# 6_Fans_Control.net
KiCad netlist of a schematic drawn in Altium Designer
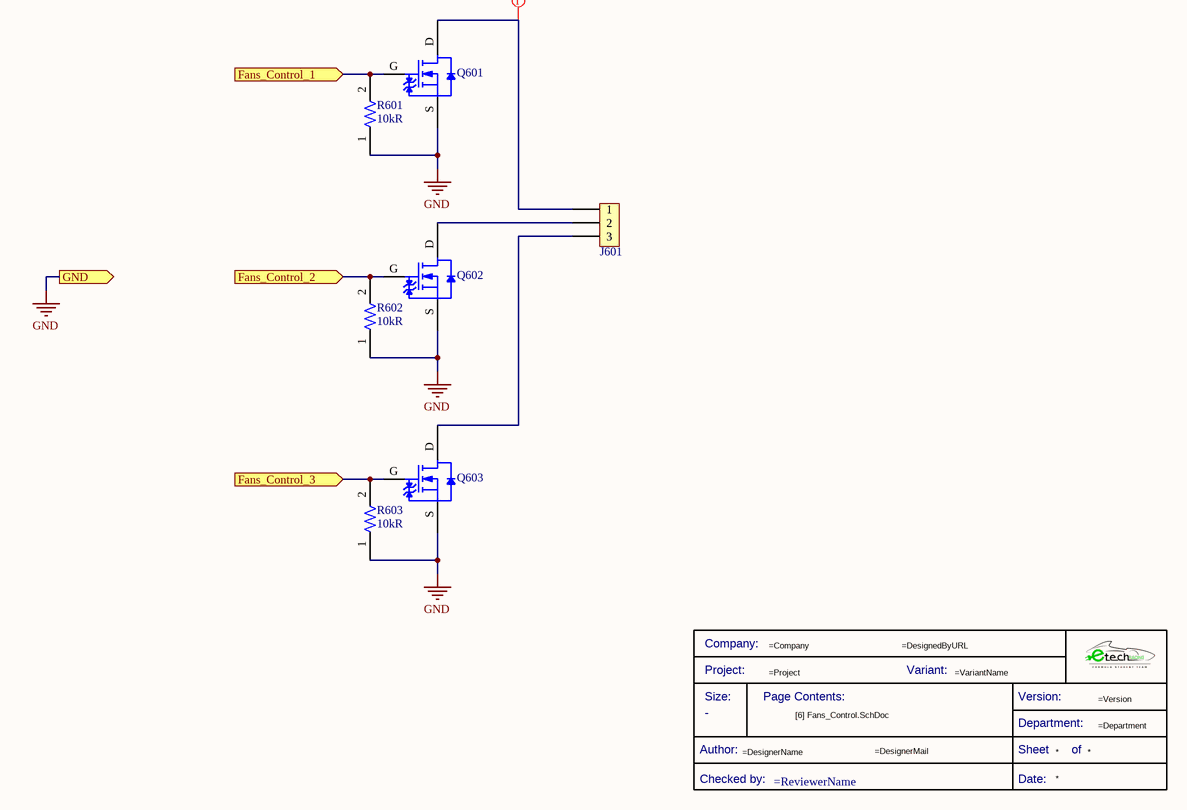
[diagram p0: [6] Fans_Control.SchDoc]

(export (version "E")
  (design (tool "Eeschema 10.0.6"))
  (components
    (comp (ref "*")
      (value "Title Block_template")
      (description "Standard Title Block")
      (fields (field (name "SIZE") "-"))
      (libsource (lib "e-Tech_Racing") (part "Title Block_template"))
    )
    (comp (ref "J601")
      (value "282836-3")
      (footprint "J_screw_1x3")
      (description "Connector, Terminal Block; Wire Receptacle; 3 Pos.; 16-30 AWG; 0.197 in. CL; Sid")
      (fields (field (name "VOLTAGE") "300V") (field (name ".CREATOR") "GP"))
      (libsource (lib "Electromechanical") (part "J_CON3x1"))
    )
    (comp (ref "Q601")
      (value "CPH3455-TL-H")
      (footprint "TRT-NCH-3/35-CPH")
      (description "CPH3455-TL-H N-channel MOSFET Transistor; 3 A; 35 V; 3-Pin CPH")
      (fields (field (name "MANUFACTURER") "ON Semiconductor") (field (name ".CREATOR") "GP"))
      (libsource (lib "Semiconductor") (part "TRT-NCH-3/35-CPH"))
    )
    (comp (ref "Q602")
      (value "CPH3455-TL-H")
      (footprint "TRT-NCH-3/35-CPH")
      (description "CPH3455-TL-H N-channel MOSFET Transistor; 3 A; 35 V; 3-Pin CPH")
      (fields (field (name "MANUFACTURER") "ON Semiconductor") (field (name ".CREATOR") "GP"))
      (libsource (lib "Semiconductor") (part "TRT-NCH-3/35-CPH"))
    )
    (comp (ref "Q603")
      (value "CPH3455-TL-H")
      (footprint "TRT-NCH-3/35-CPH")
      (description "CPH3455-TL-H N-channel MOSFET Transistor; 3 A; 35 V; 3-Pin CPH")
      (fields (field (name "MANUFACTURER") "ON Semiconductor") (field (name ".CREATOR") "GP"))
      (libsource (lib "Semiconductor") (part "TRT-NCH-3/35-CPH"))
    )
    (comp (ref "R601")
      (value "CR0805-JW-103ELF")
      (footprint "R0805FTK")
      (fields
        (field (name "TOLERANCE") "5%")
        (field (name "RESISTANCE") "10kR")
        (field (name ".CREATOR") "DR")
      )
      (libsource (lib "Passives") (part "R10k-0805FTK"))
    )
    (comp (ref "R602")
      (value "CR0805-JW-103ELF")
      (footprint "R0805FTK")
      (fields
        (field (name "TOLERANCE") "5%")
        (field (name "RESISTANCE") "10kR")
        (field (name ".CREATOR") "DR")
      )
      (libsource (lib "Passives") (part "R10k-0805FTK"))
    )
    (comp (ref "R603")
      (value "CR0805-JW-103ELF")
      (footprint "R0805FTK")
      (fields
        (field (name "TOLERANCE") "5%")
        (field (name "RESISTANCE") "10kR")
        (field (name ".CREATOR") "DR")
      )
      (libsource (lib "Passives") (part "R10k-0805FTK"))
    )
  )
  (nets
    (net (code "1") (name "/Fans_Control_1") (class "Default")
      (node (ref "Q601") (pin "G") (pinfunction "G_G") (pintype "passive"))
      (node (ref "R601") (pin "2") (pinfunction "2_2") (pintype "passive"))
    )
    (net (code "2") (name "/Fans_Control_2") (class "Default")
      (node (ref "Q602") (pin "G") (pinfunction "G_G") (pintype "passive"))
      (node (ref "R602") (pin "2") (pinfunction "2_2") (pintype "passive"))
    )
    (net (code "3") (name "/Fans_Control_3") (class "Default")
      (node (ref "Q603") (pin "G") (pinfunction "G_G") (pintype "passive"))
      (node (ref "R603") (pin "2") (pinfunction "2_2") (pintype "passive"))
    )
    (net (code "4") (name "GND") (class "Default")
      (node (ref "Q601") (pin "S") (pinfunction "S_S") (pintype "passive"))
      (node (ref "Q602") (pin "S") (pinfunction "S_S") (pintype "passive"))
      (node (ref "Q603") (pin "S") (pinfunction "S_S") (pintype "passive"))
      (node (ref "R601") (pin "1") (pinfunction "1_1") (pintype "passive"))
      (node (ref "R602") (pin "1") (pinfunction "1_1") (pintype "passive"))
      (node (ref "R603") (pin "1") (pinfunction "1_1") (pintype "passive"))
    )
    (net (code "5") (name "Net-(J601-Pad1)") (class "Default")
      (node (ref "J601") (pin "1") (pinfunction "1_1") (pintype "passive"))
      (node (ref "Q601") (pin "D") (pinfunction "D_D") (pintype "passive"))
    )
    (net (code "6") (name "Net-(J601-Pad2)") (class "Default")
      (node (ref "J601") (pin "2") (pinfunction "2_2") (pintype "passive"))
      (node (ref "Q602") (pin "D") (pinfunction "D_D") (pintype "passive"))
    )
    (net (code "7") (name "Net-(J601-Pad3)") (class "Default")
      (node (ref "J601") (pin "3") (pinfunction "3_3") (pintype "passive"))
      (node (ref "Q603") (pin "D") (pinfunction "D_D") (pintype "passive"))
    )
  )
)
